# HMI_MINI.net
KiCad netlist of a schematic drawn in Altium Designer
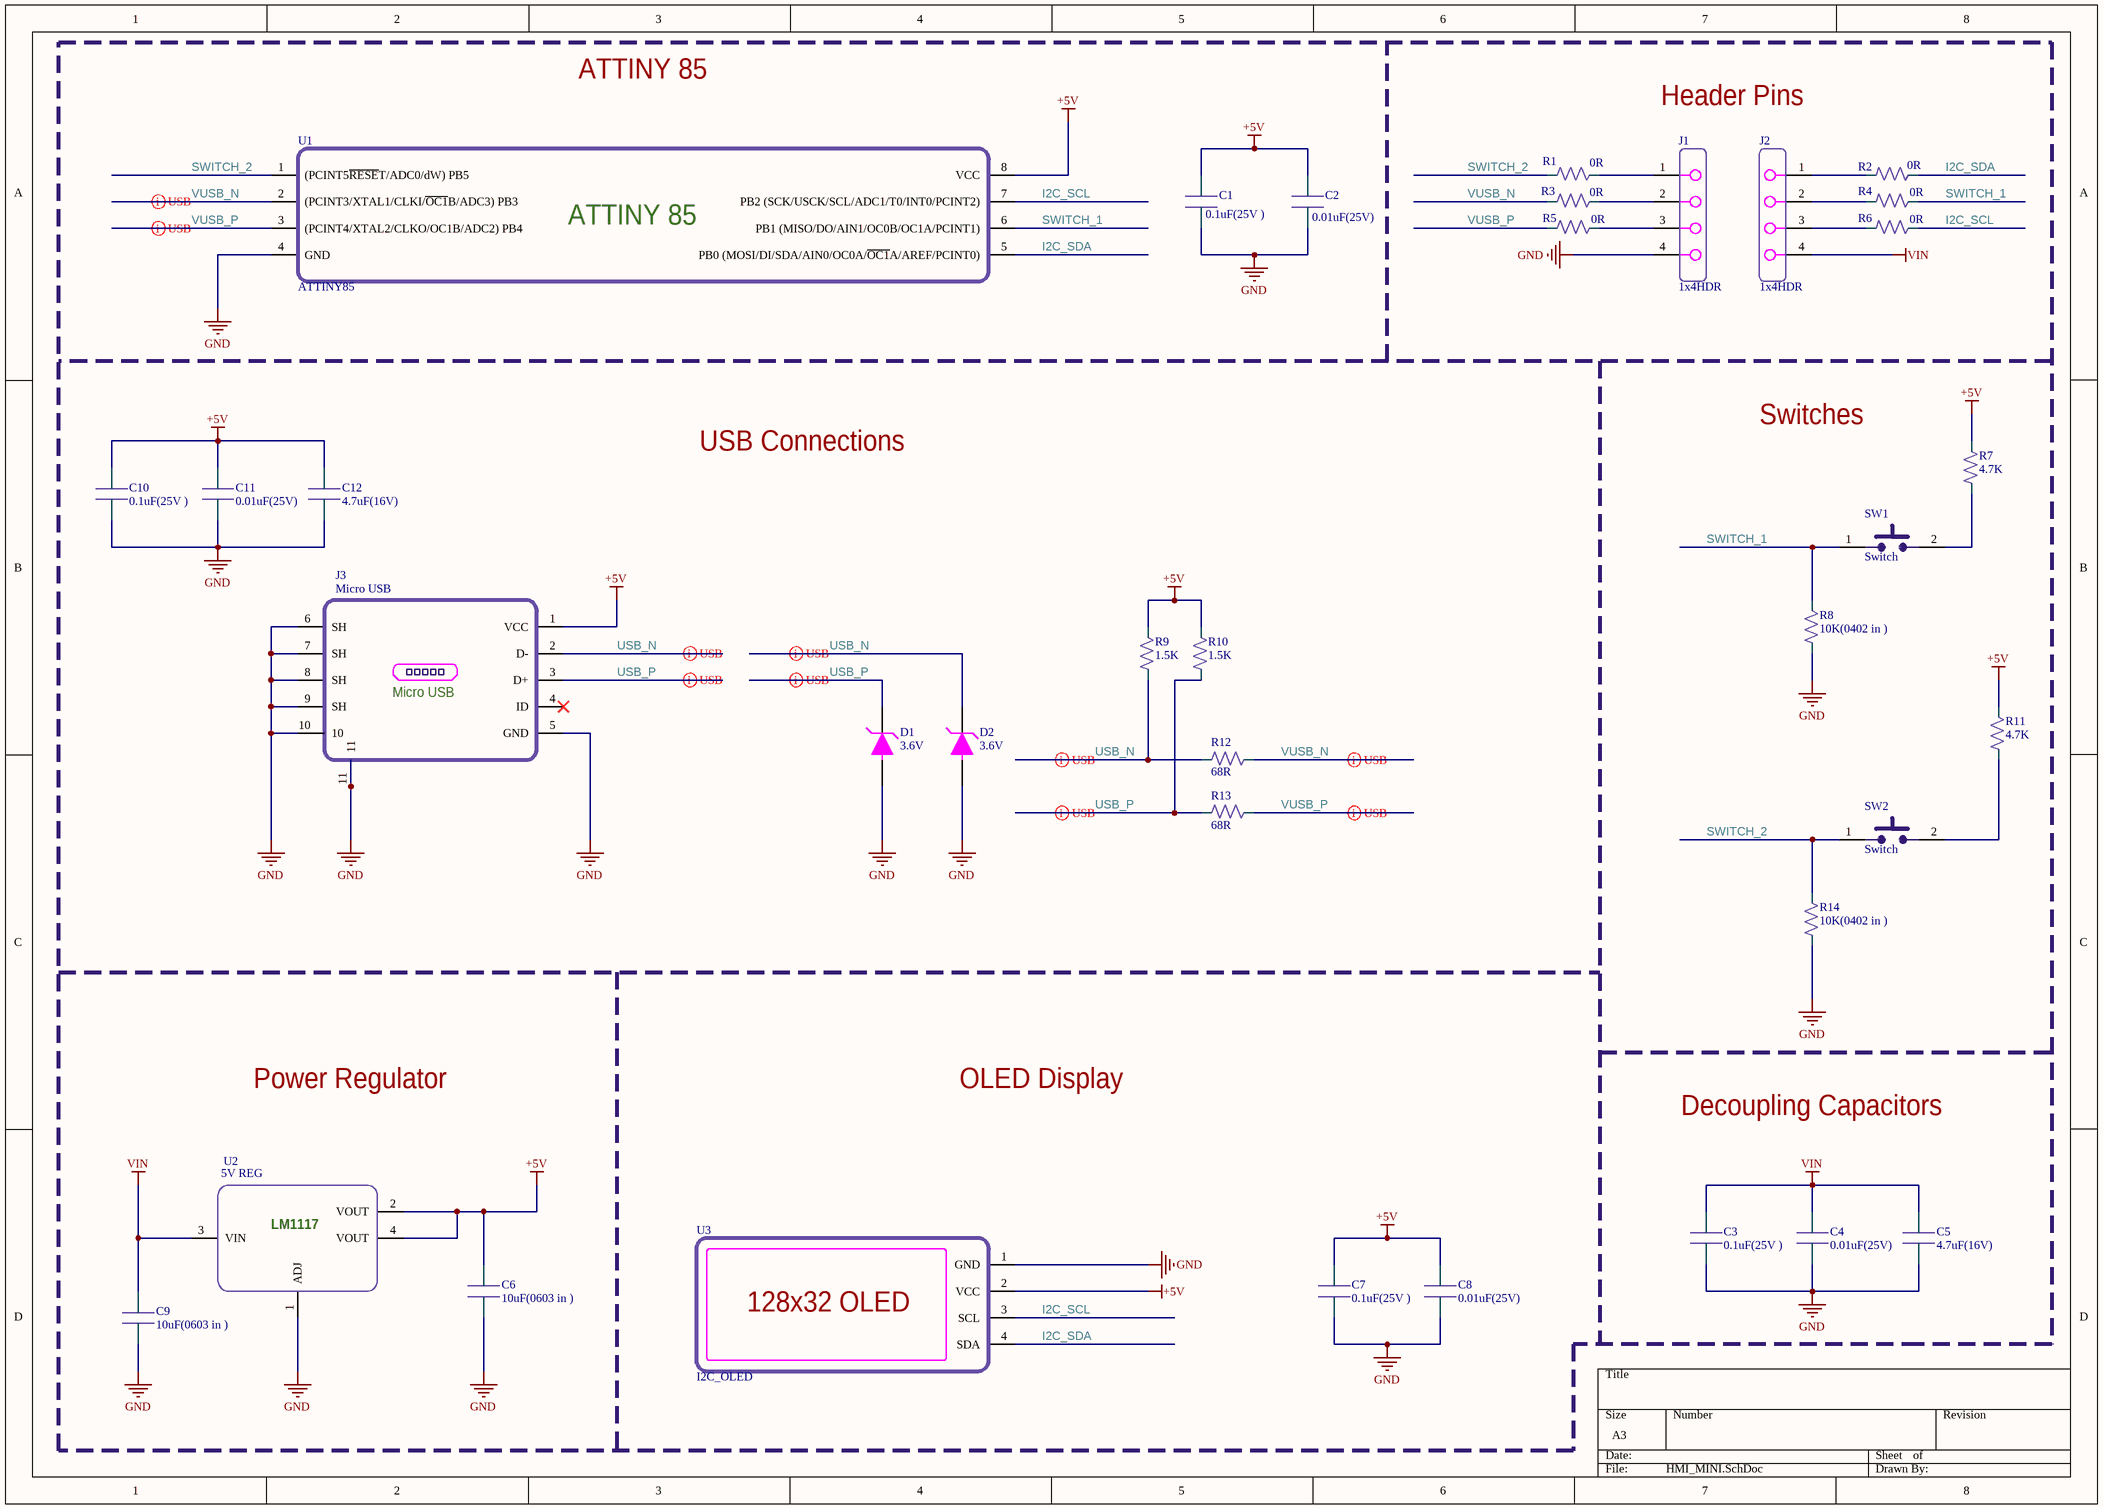
[diagram p0: HMI_MINI.SchDoc]

(export (version "E")
  (design (tool "Eeschema 10.0.6"))
  (components
    (comp (ref "C1")
      (value "0.1uF(25V )")
      (footprint "CAPACITOR_0402")
      (description "0.1µF ±10% 25V Ceramic Capacitor X7R 0402 (1005 Metric)")
      (fields
        (field (name "MANUFACTURERPARTNUMBER") "GRM155R71E104KE14J")
        (field (name "MANUFACTURER") "Murata Electronics")
      )
      (libsource (lib "Capacitors") (part "GRM155R71E104KE14J"))
    )
    (comp (ref "C2")
      (value "0.01uF(25V)")
      (footprint "CAPACITOR_0402")
      (description "10000pF ±5% 25V Ceramic Capacitor X7R 0402 (1005 Metric)")
      (fields
        (field (name "MANUFACTURERPARTNUMBER") "C0402C103J3RACTU")
        (field (name "MANUFACTURER") "KEMET")
      )
      (libsource (lib "Capacitors") (part "C0402C103J3RACTU"))
    )
    (comp (ref "C3")
      (value "0.1uF(25V )")
      (footprint "CAPACITOR_0402")
      (description "0.1µF ±10% 25V Ceramic Capacitor X7R 0402 (1005 Metric)")
      (fields
        (field (name "MANUFACTURERPARTNUMBER") "GRM155R71E104KE14J")
        (field (name "MANUFACTURER") "Murata Electronics")
      )
      (libsource (lib "Capacitors") (part "GRM155R71E104KE14J"))
    )
    (comp (ref "C4")
      (value "0.01uF(25V)")
      (footprint "CAPACITOR_0402")
      (description "10000pF ±5% 25V Ceramic Capacitor X7R 0402 (1005 Metric)")
      (fields
        (field (name "MANUFACTURERPARTNUMBER") "C0402C103J3RACTU")
        (field (name "MANUFACTURER") "KEMET")
      )
      (libsource (lib "Capacitors") (part "C0402C103J3RACTU"))
    )
    (comp (ref "C5")
      (value "4.7uF(16V)")
      (footprint "CAPACITOR_0402")
      (description "4.7µF ±20% 16V Ceramic Capacitor X5R 0402 (1005 Metric)")
      (fields
        (field (name "MANUFACTURERPARTNUMBER") "0402YD475MAT2A")
        (field (name "MANUFACTURER") "AVX Corporation")
      )
      (libsource (lib "Capacitors") (part "0402YD475MAT2A"))
    )
    (comp (ref "C6")
      (value "10uF(0603 in )")
      (footprint "Capacitor_0603")
      (description "10µF ±10% 25V Ceramic Capacitor X5R 0603 (1608 Metric)")
      (fields
        (field (name "MANUFACTURERPARTNUMBER") "GRM188R61E106KA73D")
        (field (name "MANUFACTURER") "Murata Electronics")
      )
      (libsource (lib "Capacitors") (part "GRM188R61E106KA73D"))
    )
    (comp (ref "C7")
      (value "0.1uF(25V )")
      (footprint "CAPACITOR_0402")
      (description "0.1µF ±10% 25V Ceramic Capacitor X7R 0402 (1005 Metric)")
      (fields
        (field (name "MANUFACTURERPARTNUMBER") "GRM155R71E104KE14J")
        (field (name "MANUFACTURER") "Murata Electronics")
      )
      (libsource (lib "Capacitors") (part "GRM155R71E104KE14J"))
    )
    (comp (ref "C8")
      (value "0.01uF(25V)")
      (footprint "CAPACITOR_0402")
      (description "10000pF ±5% 25V Ceramic Capacitor X7R 0402 (1005 Metric)")
      (fields
        (field (name "MANUFACTURERPARTNUMBER") "C0402C103J3RACTU")
        (field (name "MANUFACTURER") "KEMET")
      )
      (libsource (lib "Capacitors") (part "C0402C103J3RACTU"))
    )
    (comp (ref "C9")
      (value "10uF(0603 in )")
      (footprint "Capacitor_0603")
      (description "10µF ±10% 25V Ceramic Capacitor X5R 0603 (1608 Metric)")
      (fields
        (field (name "MANUFACTURERPARTNUMBER") "GRM188R61E106KA73D")
        (field (name "MANUFACTURER") "Murata Electronics")
      )
      (libsource (lib "Capacitors") (part "GRM188R61E106KA73D"))
    )
    (comp (ref "C10")
      (value "0.1uF(25V )")
      (footprint "CAPACITOR_0402")
      (description "0.1µF ±10% 25V Ceramic Capacitor X7R 0402 (1005 Metric)")
      (fields
        (field (name "MANUFACTURERPARTNUMBER") "GRM155R71E104KE14J")
        (field (name "MANUFACTURER") "Murata Electronics")
      )
      (libsource (lib "Capacitors") (part "GRM155R71E104KE14J"))
    )
    (comp (ref "C11")
      (value "0.01uF(25V)")
      (footprint "CAPACITOR_0402")
      (description "10000pF ±5% 25V Ceramic Capacitor X7R 0402 (1005 Metric)")
      (fields
        (field (name "MANUFACTURERPARTNUMBER") "C0402C103J3RACTU")
        (field (name "MANUFACTURER") "KEMET")
      )
      (libsource (lib "Capacitors") (part "C0402C103J3RACTU"))
    )
    (comp (ref "C12")
      (value "4.7uF(16V)")
      (footprint "CAPACITOR_0402")
      (description "4.7µF ±20% 16V Ceramic Capacitor X5R 0402 (1005 Metric)")
      (fields
        (field (name "MANUFACTURERPARTNUMBER") "0402YD475MAT2A")
        (field (name "MANUFACTURER") "AVX Corporation")
      )
      (libsource (lib "Capacitors") (part "0402YD475MAT2A"))
    )
    (comp (ref "D1")
      (value "3.6V")
      (footprint "SOD323_ZENER")
      (description "Zener Diode 3.6V 500mW  Surface Mount MicroMELF")
      (fields
        (field (name "MANUFACTURERPARTNUMBER") "BZM55B3V6-TR")
        (field (name "MANUFACTURER") "Vishay General Semiconductor - Diodes Division")
      )
      (libsource (lib "Diodes") (part "BZM55B3V6-TR"))
    )
    (comp (ref "D2")
      (value "3.6V")
      (footprint "SOD323_ZENER")
      (description "Zener Diode 3.6V 500mW  Surface Mount MicroMELF")
      (fields
        (field (name "MANUFACTURERPARTNUMBER") "BZM55B3V6-TR")
        (field (name "MANUFACTURER") "Vishay General Semiconductor - Diodes Division")
      )
      (libsource (lib "Diodes") (part "BZM55B3V6-TR"))
    )
    (comp (ref "J1")
      (value "1x4HDR")
      (footprint "P2.541X4HDR")
      (description "Connector Header Through Hole 4 position 0.100\" (2.54mm)")
      (fields (field (name "MANUFACTURERPARTNUMBER") "PEC04SAAN"))
      (libsource (lib "connectors") (part "PEC04SAAN"))
    )
    (comp (ref "J2")
      (value "1x4HDR")
      (footprint "P2.541X4HDR")
      (description "Connector Header Through Hole 4 position 0.100\" (2.54mm)")
      (fields (field (name "MANUFACTURERPARTNUMBER") "PEC04SAAN"))
      (libsource (lib "connectors") (part "PEC04SAAN"))
    )
    (comp (ref "J3")
      (value "Micro USB")
      (footprint "TE_1981568-1")
      (description "USB - micro B USB 2.0 Receptacle Connector 5 Position Surface Mount, Right Angle")
      (fields
        (field (name "MANUFACTURERPARTNUMBER") "1981568-1")
        (field (name "MANUFACTURER") "TE Connectivity AMP Connectors")
      )
      (libsource (lib "connectors") (part "1981568-1"))
    )
    (comp (ref "R1")
      (value "0R")
      (footprint "RESISTOR_0402")
      (fields
        (field (name "MANUFACTURERPARTNUMBER") "CR0402AJ/-000GAS")
        (field (name "MANUFACTURER") "Bourns Inc.")
      )
      (libsource (lib "Resistors") (part "CR0402AJ/-000GAS"))
    )
    (comp (ref "R2")
      (value "0R")
      (footprint "RESISTOR_0402")
      (fields
        (field (name "MANUFACTURERPARTNUMBER") "CR0402AJ/-000GAS")
        (field (name "MANUFACTURER") "Bourns Inc.")
      )
      (libsource (lib "Resistors") (part "CR0402AJ/-000GAS"))
    )
    (comp (ref "R3")
      (value "0R")
      (footprint "RESISTOR_0402")
      (fields
        (field (name "MANUFACTURERPARTNUMBER") "CR0402AJ/-000GAS")
        (field (name "MANUFACTURER") "Bourns Inc.")
      )
      (libsource (lib "Resistors") (part "CR0402AJ/-000GAS"))
    )
    (comp (ref "R4")
      (value "0R")
      (footprint "RESISTOR_0402")
      (fields
        (field (name "MANUFACTURERPARTNUMBER") "CR0402AJ/-000GAS")
        (field (name "MANUFACTURER") "Bourns Inc.")
      )
      (libsource (lib "Resistors") (part "CR0402AJ/-000GAS"))
    )
    (comp (ref "R5")
      (value "0R")
      (footprint "RESISTOR_0402")
      (fields
        (field (name "MANUFACTURERPARTNUMBER") "CR0402AJ/-000GAS")
        (field (name "MANUFACTURER") "Bourns Inc.")
      )
      (libsource (lib "Resistors") (part "CR0402AJ/-000GAS"))
    )
    (comp (ref "R6")
      (value "0R")
      (footprint "RESISTOR_0402")
      (fields
        (field (name "MANUFACTURERPARTNUMBER") "CR0402AJ/-000GAS")
        (field (name "MANUFACTURER") "Bourns Inc.")
      )
      (libsource (lib "Resistors") (part "CR0402AJ/-000GAS"))
    )
    (comp (ref "R7")
      (value "4.7K")
      (footprint "RESISTOR_0402")
      (fields
        (field (name "MANUFACTURERPARTNUMBER") "ERJ-U02J472X")
        (field (name "MANUFACTURER") "Panasonic Electronic Components")
      )
      (libsource (lib "Resistors") (part "ERJ-U02J472X"))
    )
    (comp (ref "R8")
      (value "10K(0402 in )")
      (footprint "RESISTOR_0402")
      (fields
        (field (name "MANUFACTURERPARTNUMBER") "ERJ-U02J103X")
        (field (name "MANUFACTURER") "Panasonic Electronic Components")
      )
      (libsource (lib "Resistors") (part "ERJ-U02J103X"))
    )
    (comp (ref "R9")
      (value "1.5K")
      (footprint "RESISTOR_0402")
      (fields
        (field (name "MANUFACTURERPARTNUMBER") "ERJ-U02J152X")
        (field (name "MANUFACTURER") "Panasonic Electronic Components")
      )
      (libsource (lib "Resistors") (part "ERJ-U02J152X"))
    )
    (comp (ref "R10")
      (value "1.5K")
      (footprint "RESISTOR_0402")
      (fields
        (field (name "MANUFACTURERPARTNUMBER") "ERJ-U02J152X")
        (field (name "MANUFACTURER") "Panasonic Electronic Components")
      )
      (libsource (lib "Resistors") (part "ERJ-U02J152X"))
    )
    (comp (ref "R11")
      (value "4.7K")
      (footprint "RESISTOR_0402")
      (fields
        (field (name "MANUFACTURERPARTNUMBER") "ERJ-U02J472X")
        (field (name "MANUFACTURER") "Panasonic Electronic Components")
      )
      (libsource (lib "Resistors") (part "ERJ-U02J472X"))
    )
    (comp (ref "R12")
      (value "68R")
      (footprint "RESISTOR_0402")
      (fields
        (field (name "MANUFACTURERPARTNUMBER") "CRGCQ0402J68R")
        (field (name "MANUFACTURER") "TE Connectivity Passive Product")
      )
      (libsource (lib "Resistors") (part "CRGCQ0402J68R"))
    )
    (comp (ref "R13")
      (value "68R")
      (footprint "RESISTOR_0402")
      (fields
        (field (name "MANUFACTURERPARTNUMBER") "CRGCQ0402J68R")
        (field (name "MANUFACTURER") "TE Connectivity Passive Product")
      )
      (libsource (lib "Resistors") (part "CRGCQ0402J68R"))
    )
    (comp (ref "R14")
      (value "10K(0402 in )")
      (footprint "RESISTOR_0402")
      (fields
        (field (name "MANUFACTURERPARTNUMBER") "ERJ-U02J103X")
        (field (name "MANUFACTURER") "Panasonic Electronic Components")
      )
      (libsource (lib "Resistors") (part "ERJ-U02J103X"))
    )
    (comp (ref "SW1")
      (value "Switch")
      (footprint "Switch_2Lead")
      (description "Tactile Switch SPST-NO Top Actuated Surface Mount")
      (fields
        (field (name "MANUFACTURERPARTNUMBER") "PTS636 SK50 SMTR LFS")
        (field (name "MANUFACTURER") "C&K")
      )
      (libsource (lib "connectors") (part "PTS636 SK50 SMTR LFS"))
    )
    (comp (ref "SW2")
      (value "Switch")
      (footprint "Switch_2Lead")
      (description "Tactile Switch SPST-NO Top Actuated Surface Mount")
      (fields
        (field (name "MANUFACTURERPARTNUMBER") "PTS636 SK50 SMTR LFS")
        (field (name "MANUFACTURER") "C&K")
      )
      (libsource (lib "connectors") (part "PTS636 SK50 SMTR LFS"))
    )
    (comp (ref "U1")
      (value "ATTINY85")
      (footprint "SOIC127P798X216-8N")
      (description "AVR series Microcontroller IC 8-Bit 10MHz 8KB (4K x 16) FLASH 8-SOIC")
      (fields
        (field (name "MANUFACTURERPARTNUMBER") "ATTINY85V-10SU")
        (field (name "MANUFACTURER") "Microchip Technology")
      )
      (libsource (lib "integrated_circuits") (part "ATTINY85V-10SU"))
    )
    (comp (ref "U2")
      (value "5V REG")
      (footprint "4PIN-SOT")
      (description "Linear Voltage Regulator IC Positive Fixed 1 Output  800mA SOT-223")
      (fields
        (field (name "MANUFACTURERPARTNUMBER") "LM1117IMP-5.0/NOPB")
        (field (name "MANUFACTURER") "Texas Instruments")
      )
      (libsource (lib "integrated_circuits") (part "LM1117IMP-5.0/NOPB"))
    )
    (comp (ref "U3")
      (value "I2C_OLED")
      (footprint "128x32 OLED")
      (libsource (lib "integrated_circuits") (part "I2COLED"))
    )
  )
  (nets
    (net (code "1") (name "+5V") (class "Default")
      (node (ref "C1") (pin "2") (pinfunction "2_2") (pintype "passive"))
      (node (ref "C10") (pin "2") (pinfunction "2_2") (pintype "passive"))
      (node (ref "C11") (pin "2") (pinfunction "2_2") (pintype "passive"))
      (node (ref "C12") (pin "2") (pinfunction "2_2") (pintype "passive"))
      (node (ref "C2") (pin "2") (pinfunction "2_2") (pintype "passive"))
      (node (ref "C6") (pin "2") (pinfunction "2_2") (pintype "passive"))
      (node (ref "C7") (pin "2") (pinfunction "2_2") (pintype "passive"))
      (node (ref "C8") (pin "2") (pinfunction "2_2") (pintype "passive"))
      (node (ref "J3") (pin "1") (pinfunction "VCC_1") (pintype "passive"))
      (node (ref "R10") (pin "2") (pinfunction "2_2") (pintype "passive"))
      (node (ref "R11") (pin "2") (pinfunction "2_2") (pintype "passive"))
      (node (ref "R7") (pin "2") (pinfunction "2_2") (pintype "passive"))
      (node (ref "R9") (pin "2") (pinfunction "2_2") (pintype "passive"))
      (node (ref "U1") (pin "8") (pinfunction "VCC_8") (pintype "passive"))
      (node (ref "U2") (pin "2") (pinfunction "VOUT_2") (pintype "passive"))
      (node (ref "U2") (pin "4") (pinfunction "VOUT_4") (pintype "passive"))
      (node (ref "U3") (pin "2") (pinfunction "VCC_2") (pintype "passive"))
    )
    (net (code "2") (name "/I2C_SCL") (class "Default")
      (node (ref "R6") (pin "2") (pinfunction "2_2") (pintype "passive"))
      (node (ref "U1") (pin "7") (pinfunction "PB2_(SCK/USCK/SCL/ADC1/T0/INT0/PCINT2)_7") (pintype "passive"))
      (node (ref "U3") (pin "3") (pinfunction "SCL_3") (pintype "passive"))
    )
    (net (code "3") (name "/I2C_SDA") (class "Default")
      (node (ref "R2") (pin "2") (pinfunction "2_2") (pintype "passive"))
      (node (ref "U1") (pin "5") (pinfunction "PB0_(MOSI/DI/SDA/AIN0/OC0A/~{OC1}A/AREF/PCINT0)_5") (pintype "passive"))
      (node (ref "U3") (pin "4") (pinfunction "SDA_4") (pintype "passive"))
    )
    (net (code "4") (name "/SWITCH_1") (class "Default")
      (node (ref "R4") (pin "2") (pinfunction "2_2") (pintype "passive"))
      (node (ref "R8") (pin "2") (pinfunction "2_2") (pintype "passive"))
      (node (ref "SW1") (pin "1") (pinfunction "1_1") (pintype "passive"))
      (node (ref "U1") (pin "6") (pinfunction "PB1_(MISO/DO/AIN1/OC0B/OC1A/PCINT1)_6") (pintype "passive"))
    )
    (net (code "5") (name "/SWITCH_2") (class "Default")
      (node (ref "R1") (pin "1") (pinfunction "1_1") (pintype "passive"))
      (node (ref "R14") (pin "2") (pinfunction "2_2") (pintype "passive"))
      (node (ref "SW2") (pin "1") (pinfunction "1_1") (pintype "passive"))
      (node (ref "U1") (pin "1") (pinfunction "(PCINT5~{RESE}T/ADC0/dW)_PB5_1") (pintype "passive"))
    )
    (net (code "6") (name "/USB_N") (class "Default")
      (node (ref "D2") (pin "2") (pinfunction "2_2") (pintype "passive"))
      (node (ref "J3") (pin "2") (pinfunction "D-_2") (pintype "passive"))
      (node (ref "R12") (pin "1") (pinfunction "1_1") (pintype "passive"))
      (node (ref "R9") (pin "1") (pinfunction "1_1") (pintype "passive"))
    )
    (net (code "7") (name "/USB_P") (class "Default")
      (node (ref "D1") (pin "2") (pinfunction "2_2") (pintype "passive"))
      (node (ref "J3") (pin "3") (pinfunction "D+_3") (pintype "passive"))
      (node (ref "R10") (pin "1") (pinfunction "1_1") (pintype "passive"))
      (node (ref "R13") (pin "1") (pinfunction "1_1") (pintype "passive"))
    )
    (net (code "8") (name "/VUSB_N") (class "Default")
      (node (ref "R12") (pin "2") (pinfunction "2_2") (pintype "passive"))
      (node (ref "R3") (pin "1") (pinfunction "1_1") (pintype "passive"))
      (node (ref "U1") (pin "2") (pinfunction "(PCINT3/XTAL1/CLKI/~{OC1}B/ADC3)_PB3_2") (pintype "passive"))
    )
    (net (code "9") (name "/VUSB_P") (class "Default")
      (node (ref "R13") (pin "2") (pinfunction "2_2") (pintype "passive"))
      (node (ref "R5") (pin "1") (pinfunction "1_1") (pintype "passive"))
      (node (ref "U1") (pin "3") (pinfunction "(PCINT4/XTAL2/CLKO/OC1B/ADC2)_PB4_3") (pintype "passive"))
    )
    (net (code "10") (name "GND") (class "Default")
      (node (ref "C1") (pin "1") (pinfunction "1_1") (pintype "passive"))
      (node (ref "C10") (pin "1") (pinfunction "1_1") (pintype "passive"))
      (node (ref "C11") (pin "1") (pinfunction "1_1") (pintype "passive"))
      (node (ref "C12") (pin "1") (pinfunction "1_1") (pintype "passive"))
      (node (ref "C2") (pin "1") (pinfunction "1_1") (pintype "passive"))
      (node (ref "C3") (pin "1") (pinfunction "1_1") (pintype "passive"))
      (node (ref "C4") (pin "1") (pinfunction "1_1") (pintype "passive"))
      (node (ref "C5") (pin "1") (pinfunction "1_1") (pintype "passive"))
      (node (ref "C6") (pin "1") (pinfunction "1_1") (pintype "passive"))
      (node (ref "C7") (pin "1") (pinfunction "1_1") (pintype "passive"))
      (node (ref "C8") (pin "1") (pinfunction "1_1") (pintype "passive"))
      (node (ref "C9") (pin "1") (pinfunction "1_1") (pintype "passive"))
      (node (ref "D1") (pin "1") (pinfunction "1_1") (pintype "passive"))
      (node (ref "D2") (pin "1") (pinfunction "1_1") (pintype "passive"))
      (node (ref "J1") (pin "4") (pinfunction "4_4") (pintype "passive"))
      (node (ref "J3") (pin "10") (pinfunction "10_10") (pintype "passive"))
      (node (ref "J3") (pin "11") (pinfunction "11_11") (pintype "passive"))
      (node (ref "J3") (pin "5") (pinfunction "GND_5") (pintype "passive"))
      (node (ref "J3") (pin "6") (pinfunction "SH_6") (pintype "passive"))
      (node (ref "J3") (pin "7") (pinfunction "SH_7") (pintype "passive"))
      (node (ref "J3") (pin "8") (pinfunction "SH_8") (pintype "passive"))
      (node (ref "J3") (pin "9") (pinfunction "SH_9") (pintype "passive"))
      (node (ref "R14") (pin "1") (pinfunction "1_1") (pintype "passive"))
      (node (ref "R8") (pin "1") (pinfunction "1_1") (pintype "passive"))
      (node (ref "U1") (pin "4") (pinfunction "GND_4") (pintype "passive"))
      (node (ref "U2") (pin "1") (pinfunction "ADJ_1") (pintype "passive"))
      (node (ref "U3") (pin "1") (pinfunction "GND_1") (pintype "passive"))
    )
    (net (code "11") (name "Net-(J1-Pad1)") (class "Default")
      (node (ref "J1") (pin "1") (pinfunction "1_1") (pintype "passive"))
      (node (ref "R1") (pin "2") (pinfunction "2_2") (pintype "passive"))
    )
    (net (code "12") (name "Net-(J1-Pad2)") (class "Default")
      (node (ref "J1") (pin "2") (pinfunction "2_2") (pintype "passive"))
      (node (ref "R3") (pin "2") (pinfunction "2_2") (pintype "passive"))
    )
    (net (code "13") (name "Net-(J1-Pad3)") (class "Default")
      (node (ref "J1") (pin "3") (pinfunction "3_3") (pintype "passive"))
      (node (ref "R5") (pin "2") (pinfunction "2_2") (pintype "passive"))
    )
    (net (code "14") (name "Net-(J2-Pad1)") (class "Default")
      (node (ref "J2") (pin "1") (pinfunction "1_1") (pintype "passive"))
      (node (ref "R2") (pin "1") (pinfunction "1_1") (pintype "passive"))
    )
    (net (code "15") (name "Net-(J2-Pad2)") (class "Default")
      (node (ref "J2") (pin "2") (pinfunction "2_2") (pintype "passive"))
      (node (ref "R4") (pin "1") (pinfunction "1_1") (pintype "passive"))
    )
    (net (code "16") (name "Net-(J2-Pad3)") (class "Default")
      (node (ref "J2") (pin "3") (pinfunction "3_3") (pintype "passive"))
      (node (ref "R6") (pin "1") (pinfunction "1_1") (pintype "passive"))
    )
    (net (code "17") (name "Net-(R7-Pad1)") (class "Default")
      (node (ref "R7") (pin "1") (pinfunction "1_1") (pintype "passive"))
      (node (ref "SW1") (pin "2") (pinfunction "2_2") (pintype "passive"))
    )
    (net (code "18") (name "Net-(R11-Pad1)") (class "Default")
      (node (ref "R11") (pin "1") (pinfunction "1_1") (pintype "passive"))
      (node (ref "SW2") (pin "2") (pinfunction "2_2") (pintype "passive"))
    )
    (net (code "19") (name "VIN") (class "Default")
      (node (ref "C3") (pin "2") (pinfunction "2_2") (pintype "passive"))
      (node (ref "C4") (pin "2") (pinfunction "2_2") (pintype "passive"))
      (node (ref "C5") (pin "2") (pinfunction "2_2") (pintype "passive"))
      (node (ref "C9") (pin "2") (pinfunction "2_2") (pintype "passive"))
      (node (ref "J2") (pin "4") (pinfunction "4_4") (pintype "passive"))
      (node (ref "U2") (pin "3") (pinfunction "VIN_3") (pintype "passive"))
    )
    (net (code "20") (name "unconnected-(J3-ID-Pad4)") (class "Default")
      (node (ref "J3") (pin "4") (pinfunction "ID_4") (pintype "passive+no_connect"))
    )
  )
)
